# 1_P1.net
KiCad netlist of a schematic drawn in Altium Designer
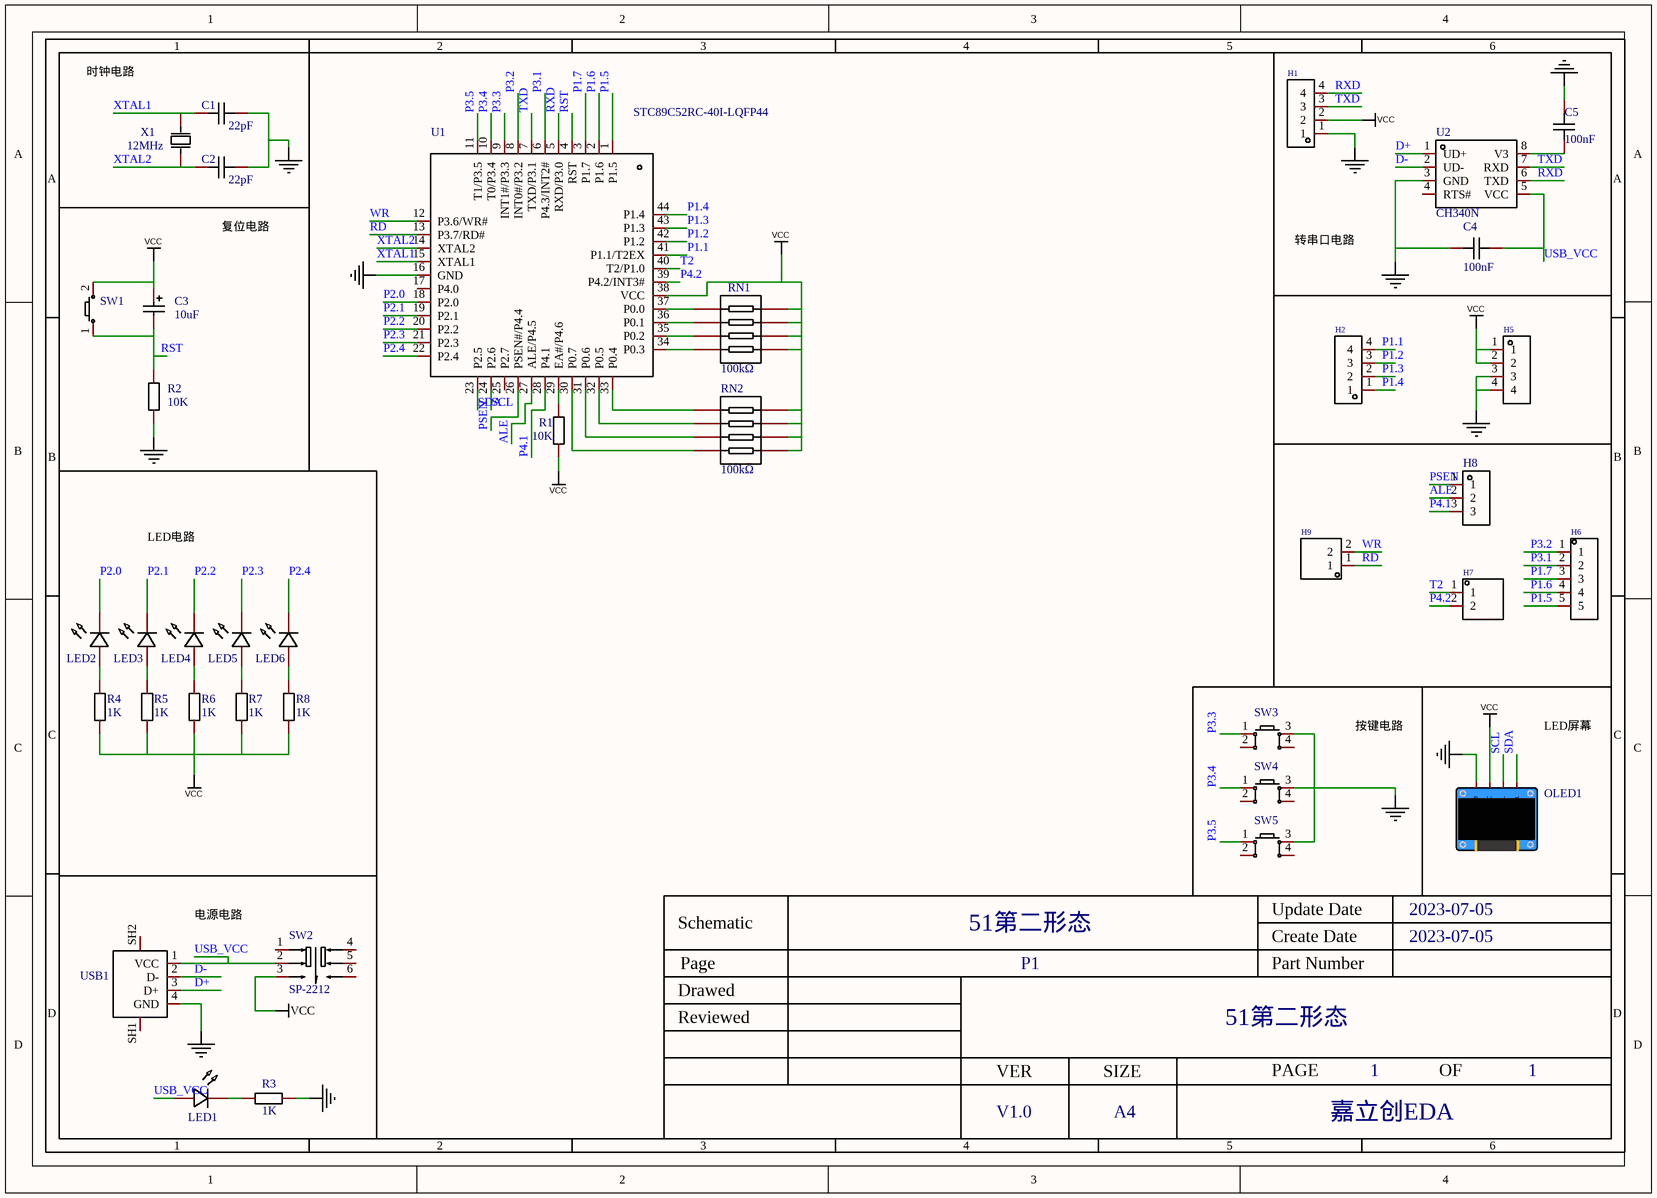
[diagram p0: 1_P1.schdoc]

(export (version "E")
  (design (tool "Eeschema 10.0.6"))
  (components
    (comp (ref "C1")
      (value "22pF")
      (description "容值:100nF;精度:±10%;额定电压:50V;材质(温度系数):X7R;")
      (fields
        (field (name "NAME") "22pF")
        (field (name "MANUFACTURER") "YAGEO(国巨)")
        (field (name "MANUFACTURER PART") "CC0603KRX7R9BB104")
      )
      (libsource (lib "altium-import") (part "root_0_CC0603KRX7R9BB104_"))
    )
    (comp (ref "C2")
      (value "22pF")
      (description "容值:100nF;精度:±10%;额定电压:50V;材质(温度系数):X7R;")
      (fields
        (field (name "NAME") "22pF")
        (field (name "MANUFACTURER") "YAGEO(国巨)")
        (field (name "MANUFACTURER PART") "CC0603KRX7R9BB104")
      )
      (libsource (lib "altium-import") (part "root_0_CC0603KRX7R9BB104_"))
    )
    (comp (ref "C3")
      (value "10uF")
      (fields (field (name "NAME") "10uF"))
      (libsource (lib "altium-import") (part "root_1_C_Ele_SMD_3x5.4mm_"))
    )
    (comp (ref "C4")
      (value "100nF")
      (fields (field (name "NAME") "100nF"))
      (libsource (lib "altium-import") (part "root_0_CAP_0603_"))
    )
    (comp (ref "C5")
      (value "100nF")
      (fields (field (name "NAME") "100nF"))
      (libsource (lib "altium-import") (part "root_1_CAP_0603_"))
    )
    (comp (ref "H1")
      (value "HDR-M_2.54_1x4P")
      (fields (field (name "MANUFACTURER") "XFCN(兴飞)") (field (name "MANUFACTURER PART") "PZ254V-11-04P"))
      (libsource (lib "altium-import") (part "root_2_HDR-M_2.54_1x4P_"))
    )
    (comp (ref "H2")
      (value "HDR-M_2.54_1x4P")
      (fields (field (name "MANUFACTURER") "XFCN(兴飞)") (field (name "MANUFACTURER PART") "PZ254V-11-04P"))
      (libsource (lib "altium-import") (part "root_2_HDR-M_2.54_1x4P_"))
    )
    (comp (ref "H5")
      (value "HDR-M_2.54_1x4P")
      (fields (field (name "MANUFACTURER") "XFCN(兴飞)") (field (name "MANUFACTURER PART") "PZ254V-11-04P"))
      (libsource (lib "altium-import") (part "root_0_HDR-M_2.54_1x4P_"))
    )
    (comp (ref "H6")
      (value "HDR-M_2.54_1x5P")
      (fields (field (name "MANUFACTURER") "MINTRON(明硕)") (field (name "MANUFACTURER PART") "MTP125-1105S1"))
      (libsource (lib "altium-import") (part "root_0_HDR-M_2.54_1x5P_"))
    )
    (comp (ref "H7")
      (value "HDR-M_2.54_1x2P")
      (fields (field (name "MANUFACTURER") "Ckmtw(灿科盟)") (field (name "MANUFACTURER PART") "B-2100S02P-A110"))
      (libsource (lib "altium-import") (part "root_0_HDR-M_2.54_1x2P_"))
    )
    (comp (ref "H8")
      (value "HDR-M_2.54_1x3P")
      (libsource (lib "altium-import") (part "root_0_HDR-M_2.54_1x3P_"))
    )
    (comp (ref "H9")
      (value "HDR-M_2.54_1x2P")
      (fields (field (name "MANUFACTURER") "Ckmtw(灿科盟)") (field (name "MANUFACTURER PART") "B-2100S02P-A110"))
      (libsource (lib "altium-import") (part "root_2_HDR-M_2.54_1x2P_"))
    )
    (comp (ref "LED1") (value "LED_TH-R_3mm") (libsource (lib "altium-import") (part "root_0_LED_TH-R_3mm_")))
    (comp (ref "LED2") (value "LED_TH-R_3mm") (libsource (lib "altium-import") (part "root_1_LED_TH-R_3mm_")))
    (comp (ref "LED3") (value "LED_TH-R_3mm") (libsource (lib "altium-import") (part "root_1_LED_TH-R_3mm_")))
    (comp (ref "LED4") (value "LED_TH-R_3mm") (libsource (lib "altium-import") (part "root_1_LED_TH-R_3mm_")))
    (comp (ref "LED5") (value "LED_TH-R_3mm") (libsource (lib "altium-import") (part "root_1_LED_TH-R_3mm_")))
    (comp (ref "LED6") (value "LED_TH-R_3mm") (libsource (lib "altium-import") (part "root_1_LED_TH-R_3mm_")))
    (comp (ref "OLED1")
      (value "0.96OLED模块_4P")
      (libsource (lib "altium-import") (part "root_0_0.96OLED模块_4P_"))
    )
    (comp (ref "R1")
      (value "10K")
      (fields (field (name "NAME") "10K"))
      (libsource (lib "altium-import") (part "root_1_Res_0603_"))
    )
    (comp (ref "R2")
      (value "10K")
      (fields (field (name "NAME") "10K"))
      (libsource (lib "altium-import") (part "root_1_Res_0603_"))
    )
    (comp (ref "R3")
      (value "1K")
      (fields (field (name "NAME") "1K"))
      (libsource (lib "altium-import") (part "root_0_Res_0603_"))
    )
    (comp (ref "R4")
      (value "1K")
      (fields (field (name "NAME") "1K"))
      (libsource (lib "altium-import") (part "root_1_Res_0603_"))
    )
    (comp (ref "R5")
      (value "1K")
      (fields (field (name "NAME") "1K"))
      (libsource (lib "altium-import") (part "root_1_Res_0603_"))
    )
    (comp (ref "R6")
      (value "1K")
      (fields (field (name "NAME") "1K"))
      (libsource (lib "altium-import") (part "root_1_Res_0603_"))
    )
    (comp (ref "R7")
      (value "1K")
      (fields (field (name "NAME") "1K"))
      (libsource (lib "altium-import") (part "root_1_Res_0603_"))
    )
    (comp (ref "R8")
      (value "1K")
      (fields (field (name "NAME") "1K"))
      (libsource (lib "altium-import") (part "root_1_Res_0603_"))
    )
    (comp (ref "RN1")
      (value "100kΩ")
      (description "阻值:10kΩ;精度:±5%;单个元件功率:62.5mW;电阻器数:4;")
      (fields
        (field (name "NAME") "100kΩ")
        (field (name "MANUFACTURER") "UNI-ROYAL(厚声)")
        (field (name "MANUFACTURER PART") "4D03WGJ0103T5E")
      )
      (libsource (lib "altium-import") (part "root_0_4D03WGJ0103T5E_"))
    )
    (comp (ref "RN2")
      (value "100kΩ")
      (description "阻值:10kΩ;精度:±5%;单个元件功率:62.5mW;电阻器数:4;")
      (fields
        (field (name "NAME") "100kΩ")
        (field (name "MANUFACTURER") "UNI-ROYAL(厚声)")
        (field (name "MANUFACTURER PART") "4D03WGJ0103T5E")
      )
      (libsource (lib "altium-import") (part "root_2_4D03WGJ0103T5E_"))
    )
    (comp (ref "SW1")
      (value "Key_SMD_3x4x2")
      (libsource (lib "altium-import") (part "root_1_Key_SMD_3x4x2_"))
    )
    (comp (ref "SW2")
      (value "SP-2212")
      (fields (field (name "NAME") "SP-2212") (field (name "MANUFACTURER") "RISHENG(日昇)"))
      (libsource (lib "altium-import") (part "root_3_SP-2212_"))
    )
    (comp (ref "SW3")
      (value "Key_SMD_12x12x7.3")
      (libsource (lib "altium-import") (part "root_0_Key_SMD_12x12x7.3_"))
    )
    (comp (ref "SW4")
      (value "Key_SMD_12x12x7.3")
      (libsource (lib "altium-import") (part "root_0_Key_SMD_12x12x7.3_"))
    )
    (comp (ref "SW5")
      (value "Key_SMD_12x12x7.3")
      (libsource (lib "altium-import") (part "root_0_Key_SMD_12x12x7.3_"))
    )
    (comp (ref "U1")
      (value "STC89C52RC-40I-LQFP44")
      (description "CPU内核:51系列;CPU最大主频:-;程序存储容量:8KB;程序存储器类型:FLASH;RAM总容量:512Byte;GPIO端口数量:39;")
      (fields (field (name "NAME") "STC89C52RC-40I-LQFP44") (field (name "MANUFACTURER") "STC(宏晶)"))
      (libsource (lib "altium-import") (part "root_3_STC89C52RC-40I-LQFP44_"))
    )
    (comp (ref "U2")
      (value "CH340N")
      (fields (field (name "NAME") "CH340N") (field (name "MANUFACTURER") "WCH(南京沁恒)"))
      (libsource (lib "altium-import") (part "root_0_CH340N_"))
    )
    (comp (ref "USB1") (value "USB_ Type-A") (libsource (lib "altium-import") (part "root_0_USB_ Type-A_")))
    (comp (ref "X1")
      (value "12MHz")
      (description "频率:12MHz;频率公差:±20ppm;负载电容:20pF;")
      (fields
        (field (name "NAME") "12MHz")
        (field (name "MANUFACTURER") "YXC(扬兴晶振)")
        (field (name "MANUFACTURER PART") "X49SD12MSD2SC")
      )
      (libsource (lib "altium-import") (part "root_1_X49SD12MSD2SC_"))
    )
  )
  (nets
    (net (code "1") (name "/ALE") (class "Default")
      (node (ref "H8") (pin "2") (pinfunction "2_2") (pintype "passive"))
      (node (ref "U1") (pin "27") (pinfunction "ALE/P4.5_27") (pintype "passive"))
    )
    (net (code "2") (name "/D+") (class "Default")
      (node (ref "U2") (pin "1") (pinfunction "UD+_1") (pintype "passive"))
      (node (ref "USB1") (pin "3") (pinfunction "D+_3") (pintype "passive"))
    )
    (net (code "3") (name "/D-") (class "Default")
      (node (ref "U2") (pin "2") (pinfunction "UD-_2") (pintype "passive"))
      (node (ref "USB1") (pin "2") (pinfunction "D-_2") (pintype "passive"))
    )
    (net (code "4") (name "/P1.1") (class "Default")
      (node (ref "H2") (pin "4") (pinfunction "4_4") (pintype "passive"))
      (node (ref "U1") (pin "41") (pinfunction "P1.1/T2EX_41") (pintype "passive"))
    )
    (net (code "5") (name "/P1.2") (class "Default")
      (node (ref "H2") (pin "3") (pinfunction "3_3") (pintype "passive"))
      (node (ref "U1") (pin "42") (pinfunction "P1.2_42") (pintype "passive"))
    )
    (net (code "6") (name "/P1.3") (class "Default")
      (node (ref "H2") (pin "2") (pinfunction "2_2") (pintype "passive"))
      (node (ref "U1") (pin "43") (pinfunction "P1.3_43") (pintype "passive"))
    )
    (net (code "7") (name "/P1.4") (class "Default")
      (node (ref "H2") (pin "1") (pinfunction "1_1") (pintype "passive"))
      (node (ref "U1") (pin "44") (pinfunction "P1.4_44") (pintype "passive"))
    )
    (net (code "8") (name "/P1.5") (class "Default")
      (node (ref "H6") (pin "5") (pinfunction "5_5") (pintype "passive"))
      (node (ref "U1") (pin "1") (pinfunction "P1.5_1") (pintype "passive"))
    )
    (net (code "9") (name "/P1.6") (class "Default")
      (node (ref "H6") (pin "4") (pinfunction "4_4") (pintype "passive"))
      (node (ref "U1") (pin "2") (pinfunction "P1.6_2") (pintype "passive"))
    )
    (net (code "10") (name "/P1.7") (class "Default")
      (node (ref "H6") (pin "3") (pinfunction "3_3") (pintype "passive"))
      (node (ref "U1") (pin "3") (pinfunction "P1.7_3") (pintype "passive"))
    )
    (net (code "11") (name "/P2.0") (class "Default")
      (node (ref "LED2") (pin "2") (pinfunction "A_2") (pintype "passive"))
      (node (ref "U1") (pin "18") (pinfunction "P2.0_18") (pintype "passive"))
    )
    (net (code "12") (name "/P2.1") (class "Default")
      (node (ref "LED3") (pin "2") (pinfunction "A_2") (pintype "passive"))
      (node (ref "U1") (pin "19") (pinfunction "P2.1_19") (pintype "passive"))
    )
    (net (code "13") (name "/P2.2") (class "Default")
      (node (ref "LED4") (pin "2") (pinfunction "A_2") (pintype "passive"))
      (node (ref "U1") (pin "20") (pinfunction "P2.2_20") (pintype "passive"))
    )
    (net (code "14") (name "/P2.3") (class "Default")
      (node (ref "LED5") (pin "2") (pinfunction "A_2") (pintype "passive"))
      (node (ref "U1") (pin "21") (pinfunction "P2.3_21") (pintype "passive"))
    )
    (net (code "15") (name "/P2.4") (class "Default")
      (node (ref "LED6") (pin "2") (pinfunction "A_2") (pintype "passive"))
      (node (ref "U1") (pin "22") (pinfunction "P2.4_22") (pintype "passive"))
    )
    (net (code "16") (name "/P3.1") (class "Default")
      (node (ref "H6") (pin "2") (pinfunction "2_2") (pintype "passive"))
      (node (ref "U1") (pin "6") (pinfunction "P4.3/INT2#_6") (pintype "passive"))
    )
    (net (code "17") (name "/P3.2") (class "Default")
      (node (ref "H6") (pin "1") (pinfunction "1_1") (pintype "passive"))
      (node (ref "U1") (pin "8") (pinfunction "INT0#/P3.2_8") (pintype "passive"))
    )
    (net (code "18") (name "/P3.3") (class "Default")
      (node (ref "SW3") (pin "1") (pinfunction "1_1") (pintype "passive"))
      (node (ref "U1") (pin "9") (pinfunction "INT1#/P3.3_9") (pintype "passive"))
    )
    (net (code "19") (name "/P3.4") (class "Default")
      (node (ref "SW4") (pin "1") (pinfunction "1_1") (pintype "passive"))
      (node (ref "U1") (pin "10") (pinfunction "T0/P3.4_10") (pintype "passive"))
    )
    (net (code "20") (name "/P3.5") (class "Default")
      (node (ref "SW5") (pin "1") (pinfunction "1_1") (pintype "passive"))
      (node (ref "U1") (pin "11") (pinfunction "T1/P3.5_11") (pintype "passive"))
    )
    (net (code "21") (name "/P4.1") (class "Default")
      (node (ref "H8") (pin "3") (pinfunction "3_3") (pintype "passive"))
      (node (ref "U1") (pin "28") (pinfunction "P4.1_28") (pintype "passive"))
    )
    (net (code "22") (name "/P4.2") (class "Default")
      (node (ref "H7") (pin "2") (pinfunction "2_2") (pintype "passive"))
      (node (ref "U1") (pin "39") (pinfunction "P4.2/INT3#_39") (pintype "passive"))
    )
    (net (code "23") (name "/PSEN") (class "Default")
      (node (ref "H8") (pin "1") (pinfunction "1_1") (pintype "passive"))
      (node (ref "U1") (pin "26") (pinfunction "PSEN#/P4.4_26") (pintype "passive"))
    )
    (net (code "24") (name "/RD") (class "Default")
      (node (ref "H9") (pin "1") (pinfunction "1_1") (pintype "passive"))
      (node (ref "U1") (pin "13") (pinfunction "P3.7/RD#_13") (pintype "passive"))
    )
    (net (code "25") (name "/RST") (class "Default")
      (node (ref "C3") (pin "2") (pinfunction "2_2") (pintype "passive"))
      (node (ref "R2") (pin "2") (pinfunction "2_2") (pintype "passive"))
      (node (ref "SW1") (pin "1") (pinfunction "1_1") (pintype "passive"))
      (node (ref "U1") (pin "4") (pinfunction "RST_4") (pintype "passive"))
    )
    (net (code "26") (name "/RXD") (class "Default")
      (node (ref "H1") (pin "4") (pinfunction "4_4") (pintype "passive"))
      (node (ref "U1") (pin "5") (pinfunction "RXD/P3.0_5") (pintype "passive"))
      (node (ref "U2") (pin "6") (pinfunction "TXD_6") (pintype "passive"))
    )
    (net (code "27") (name "/SCL") (class "Default")
      (node (ref "OLED1") (pin "3") (pinfunction "SCL_3") (pintype "passive"))
      (node (ref "U1") (pin "24") (pinfunction "P2.6_24") (pintype "passive"))
    )
    (net (code "28") (name "/SDA") (class "Default")
      (node (ref "OLED1") (pin "4") (pinfunction "SDA_4") (pintype "passive"))
      (node (ref "U1") (pin "23") (pinfunction "P2.5_23") (pintype "passive"))
    )
    (net (code "29") (name "/T2") (class "Default")
      (node (ref "H7") (pin "1") (pinfunction "1_1") (pintype "passive"))
      (node (ref "U1") (pin "40") (pinfunction "T2/P1.0_40") (pintype "passive"))
    )
    (net (code "30") (name "/TXD") (class "Default")
      (node (ref "H1") (pin "3") (pinfunction "3_3") (pintype "passive"))
      (node (ref "U1") (pin "7") (pinfunction "TXD/P3.1_7") (pintype "passive"))
      (node (ref "U2") (pin "7") (pinfunction "RXD_7") (pintype "passive"))
    )
    (net (code "31") (name "/USB_VCC") (class "Default")
      (node (ref "C4") (pin "2") (pinfunction "2_2") (pintype "passive"))
      (node (ref "LED1") (pin "1") (pinfunction "C_1") (pintype "passive"))
      (node (ref "SW2") (pin "2") (pinfunction "2_2") (pintype "passive"))
      (node (ref "U2") (pin "5") (pinfunction "VCC_5") (pintype "passive"))
      (node (ref "USB1") (pin "1") (pinfunction "VCC_1") (pintype "passive"))
    )
    (net (code "32") (name "/WR") (class "Default")
      (node (ref "H9") (pin "2") (pinfunction "2_2") (pintype "passive"))
      (node (ref "U1") (pin "12") (pinfunction "P3.6/WR#_12") (pintype "passive"))
    )
    (net (code "33") (name "/XTAL1") (class "Default")
      (node (ref "C1") (pin "1") (pinfunction "1_1") (pintype "passive"))
      (node (ref "U1") (pin "15") (pinfunction "XTAL1_15") (pintype "passive"))
      (node (ref "X1") (pin "1") (pinfunction "OSC1_1") (pintype "passive"))
    )
    (net (code "34") (name "/XTAL2") (class "Default")
      (node (ref "C2") (pin "1") (pinfunction "1_1") (pintype "passive"))
      (node (ref "U1") (pin "14") (pinfunction "XTAL2_14") (pintype "passive"))
      (node (ref "X1") (pin "2") (pinfunction "OSC2_2") (pintype "passive"))
    )
    (net (code "35") (name "<NO NET>") (class "Default")
      (node (ref "C1") (pin "2") (pinfunction "2_2") (pintype "passive"))
      (node (ref "C2") (pin "2") (pinfunction "2_2") (pintype "passive"))
      (node (ref "C4") (pin "1") (pinfunction "1_1") (pintype "passive"))
      (node (ref "C5") (pin "2") (pinfunction "2_2") (pintype "passive"))
      (node (ref "H1") (pin "1") (pinfunction "1_1") (pintype "passive"))
      (node (ref "H5") (pin "3") (pinfunction "3_3") (pintype "passive"))
      (node (ref "H5") (pin "4") (pinfunction "4_4") (pintype "passive"))
      (node (ref "OLED1") (pin "1") (pinfunction "GND_1") (pintype "passive"))
      (node (ref "R2") (pin "1") (pinfunction "1_1") (pintype "passive"))
      (node (ref "R3") (pin "2") (pinfunction "2_2") (pintype "passive"))
      (node (ref "SW3") (pin "3") (pinfunction "3_3") (pintype "passive"))
      (node (ref "SW4") (pin "3") (pinfunction "3_3") (pintype "passive"))
      (node (ref "SW5") (pin "3") (pinfunction "3_3") (pintype "passive"))
      (node (ref "U1") (pin "16") (pinfunction "GND_16") (pintype "passive"))
      (node (ref "U2") (pin "3") (pinfunction "GND_3") (pintype "passive"))
      (node (ref "USB1") (pin "4") (pinfunction "GND_4") (pintype "passive"))
    )
    (net (code "36") (name "Net-(LED1-A)") (class "Default")
      (node (ref "LED1") (pin "2") (pinfunction "A_2") (pintype "passive"))
      (node (ref "R3") (pin "1") (pinfunction "1_1") (pintype "passive"))
    )
    (net (code "37") (name "Net-(LED2-C)") (class "Default")
      (node (ref "LED2") (pin "1") (pinfunction "C_1") (pintype "passive"))
      (node (ref "R4") (pin "2") (pinfunction "2_2") (pintype "passive"))
    )
    (net (code "38") (name "Net-(LED3-C)") (class "Default")
      (node (ref "LED3") (pin "1") (pinfunction "C_1") (pintype "passive"))
      (node (ref "R5") (pin "2") (pinfunction "2_2") (pintype "passive"))
    )
    (net (code "39") (name "Net-(LED4-C)") (class "Default")
      (node (ref "LED4") (pin "1") (pinfunction "C_1") (pintype "passive"))
      (node (ref "R6") (pin "2") (pinfunction "2_2") (pintype "passive"))
    )
    (net (code "40") (name "Net-(LED5-C)") (class "Default")
      (node (ref "LED5") (pin "1") (pinfunction "C_1") (pintype "passive"))
      (node (ref "R7") (pin "2") (pinfunction "2_2") (pintype "passive"))
    )
    (net (code "41") (name "Net-(LED6-C)") (class "Default")
      (node (ref "LED6") (pin "1") (pinfunction "C_1") (pintype "passive"))
      (node (ref "R8") (pin "2") (pinfunction "2_2") (pintype "passive"))
    )
    (net (code "42") (name "Net-(U1-EA#{slash}P4.6)") (class "Default")
      (node (ref "R1") (pin "2") (pinfunction "2_2") (pintype "passive"))
      (node (ref "U1") (pin "29") (pinfunction "EA#/P4.6_29") (pintype "passive"))
    )
    (net (code "43") (name "Net-(U1-P0.0)") (class "Default")
      (node (ref "RN1") (pin "1") (pinfunction "1_1") (pintype "passive"))
      (node (ref "U1") (pin "37") (pinfunction "P0.0_37") (pintype "passive"))
    )
    (net (code "44") (name "Net-(U1-P0.1)") (class "Default")
      (node (ref "RN1") (pin "2") (pinfunction "2_2") (pintype "passive"))
      (node (ref "U1") (pin "36") (pinfunction "P0.1_36") (pintype "passive"))
    )
    (net (code "45") (name "Net-(U1-P0.2)") (class "Default")
      (node (ref "RN1") (pin "3") (pinfunction "3_3") (pintype "passive"))
      (node (ref "U1") (pin "35") (pinfunction "P0.2_35") (pintype "passive"))
    )
    (net (code "46") (name "Net-(U1-P0.3)") (class "Default")
      (node (ref "RN1") (pin "4") (pinfunction "4_4") (pintype "passive"))
      (node (ref "U1") (pin "34") (pinfunction "P0.3_34") (pintype "passive"))
    )
    (net (code "47") (name "Net-(U1-P0.4)") (class "Default")
      (node (ref "RN2") (pin "5") (pinfunction "5_5") (pintype "passive"))
      (node (ref "U1") (pin "33") (pinfunction "P0.4_33") (pintype "passive"))
    )
    (net (code "48") (name "Net-(U1-P0.5)") (class "Default")
      (node (ref "RN2") (pin "6") (pinfunction "6_6") (pintype "passive"))
      (node (ref "U1") (pin "32") (pinfunction "P0.5_32") (pintype "passive"))
    )
    (net (code "49") (name "Net-(U1-P0.6)") (class "Default")
      (node (ref "RN2") (pin "7") (pinfunction "7_7") (pintype "passive"))
      (node (ref "U1") (pin "31") (pinfunction "P0.6_31") (pintype "passive"))
    )
    (net (code "50") (name "Net-(U1-P0.7)") (class "Default")
      (node (ref "RN2") (pin "8") (pinfunction "8_8") (pintype "passive"))
      (node (ref "U1") (pin "30") (pinfunction "P0.7_30") (pintype "passive"))
    )
    (net (code "51") (name "Net-(U2-V3)") (class "Default")
      (node (ref "C5") (pin "1") (pinfunction "1_1") (pintype "passive"))
      (node (ref "U2") (pin "8") (pinfunction "V3_8") (pintype "passive"))
    )
    (net (code "52") (name "VCC") (class "Default")
      (node (ref "C3") (pin "1") (pinfunction "1_1") (pintype "passive"))
      (node (ref "H1") (pin "2") (pinfunction "2_2") (pintype "passive"))
      (node (ref "H5") (pin "1") (pinfunction "1_1") (pintype "passive"))
      (node (ref "H5") (pin "2") (pinfunction "2_2") (pintype "passive"))
      (node (ref "OLED1") (pin "2") (pinfunction "VCC_2") (pintype "passive"))
      (node (ref "R1") (pin "1") (pinfunction "1_1") (pintype "passive"))
      (node (ref "R4") (pin "1") (pinfunction "1_1") (pintype "passive"))
      (node (ref "R5") (pin "1") (pinfunction "1_1") (pintype "passive"))
      (node (ref "R6") (pin "1") (pinfunction "1_1") (pintype "passive"))
      (node (ref "R7") (pin "1") (pinfunction "1_1") (pintype "passive"))
      (node (ref "R8") (pin "1") (pinfunction "1_1") (pintype "passive"))
      (node (ref "RN1") (pin "5") (pinfunction "5_5") (pintype "passive"))
      (node (ref "RN1") (pin "6") (pinfunction "6_6") (pintype "passive"))
      (node (ref "RN1") (pin "7") (pinfunction "7_7") (pintype "passive"))
      (node (ref "RN1") (pin "8") (pinfunction "8_8") (pintype "passive"))
      (node (ref "RN2") (pin "1") (pinfunction "1_1") (pintype "passive"))
      (node (ref "RN2") (pin "2") (pinfunction "2_2") (pintype "passive"))
      (node (ref "RN2") (pin "3") (pinfunction "3_3") (pintype "passive"))
      (node (ref "RN2") (pin "4") (pinfunction "4_4") (pintype "passive"))
      (node (ref "SW1") (pin "2") (pinfunction "2_2") (pintype "passive"))
      (node (ref "SW2") (pin "3") (pinfunction "3_3") (pintype "passive"))
      (node (ref "U1") (pin "38") (pinfunction "VCC_38") (pintype "passive"))
    )
    (net (code "53") (name "unconnected-(SW2-Pad1)") (class "Default")
      (node (ref "SW2") (pin "1") (pinfunction "1_1") (pintype "passive"))
    )
    (net (code "54") (name "unconnected-(SW2-Pad4)") (class "Default")
      (node (ref "SW2") (pin "4") (pinfunction "4_4") (pintype "passive"))
    )
    (net (code "55") (name "unconnected-(SW2-Pad5)") (class "Default")
      (node (ref "SW2") (pin "5") (pinfunction "5_5") (pintype "passive"))
    )
    (net (code "56") (name "unconnected-(SW2-Pad6)") (class "Default")
      (node (ref "SW2") (pin "6") (pinfunction "6_6") (pintype "passive"))
    )
    (net (code "57") (name "unconnected-(SW3-Pad2)") (class "Default")
      (node (ref "SW3") (pin "2") (pinfunction "2_2") (pintype "passive"))
    )
    (net (code "58") (name "unconnected-(SW3-Pad4)") (class "Default")
      (node (ref "SW3") (pin "4") (pinfunction "4_4") (pintype "passive"))
    )
    (net (code "59") (name "unconnected-(SW4-Pad2)") (class "Default")
      (node (ref "SW4") (pin "2") (pinfunction "2_2") (pintype "passive"))
    )
    (net (code "60") (name "unconnected-(SW4-Pad4)") (class "Default")
      (node (ref "SW4") (pin "4") (pinfunction "4_4") (pintype "passive"))
    )
    (net (code "61") (name "unconnected-(SW5-Pad2)") (class "Default")
      (node (ref "SW5") (pin "2") (pinfunction "2_2") (pintype "passive"))
    )
    (net (code "62") (name "unconnected-(SW5-Pad4)") (class "Default")
      (node (ref "SW5") (pin "4") (pinfunction "4_4") (pintype "passive"))
    )
    (net (code "63") (name "unconnected-(U1-P2.7-Pad25)") (class "Default")
      (node (ref "U1") (pin "25") (pinfunction "P2.7_25") (pintype "passive"))
    )
    (net (code "64") (name "unconnected-(U1-P4.0-Pad17)") (class "Default")
      (node (ref "U1") (pin "17") (pinfunction "P4.0_17") (pintype "passive"))
    )
    (net (code "65") (name "unconnected-(U2-RTS#-Pad4)") (class "Default")
      (node (ref "U2") (pin "4") (pinfunction "RTS#_4") (pintype "passive"))
    )
    (net (code "66") (name "unconnected-(USB1-PadSH1)") (class "Default")
      (node (ref "USB1") (pin "SH1") (pinfunction "SH1_SH1") (pintype "passive"))
    )
    (net (code "67") (name "unconnected-(USB1-PadSH2)") (class "Default")
      (node (ref "USB1") (pin "SH2") (pinfunction "SH2_SH2") (pintype "passive"))
    )
  )
)
